# 3_Sensor.net
KiCad netlist of a schematic drawn in Altium Designer
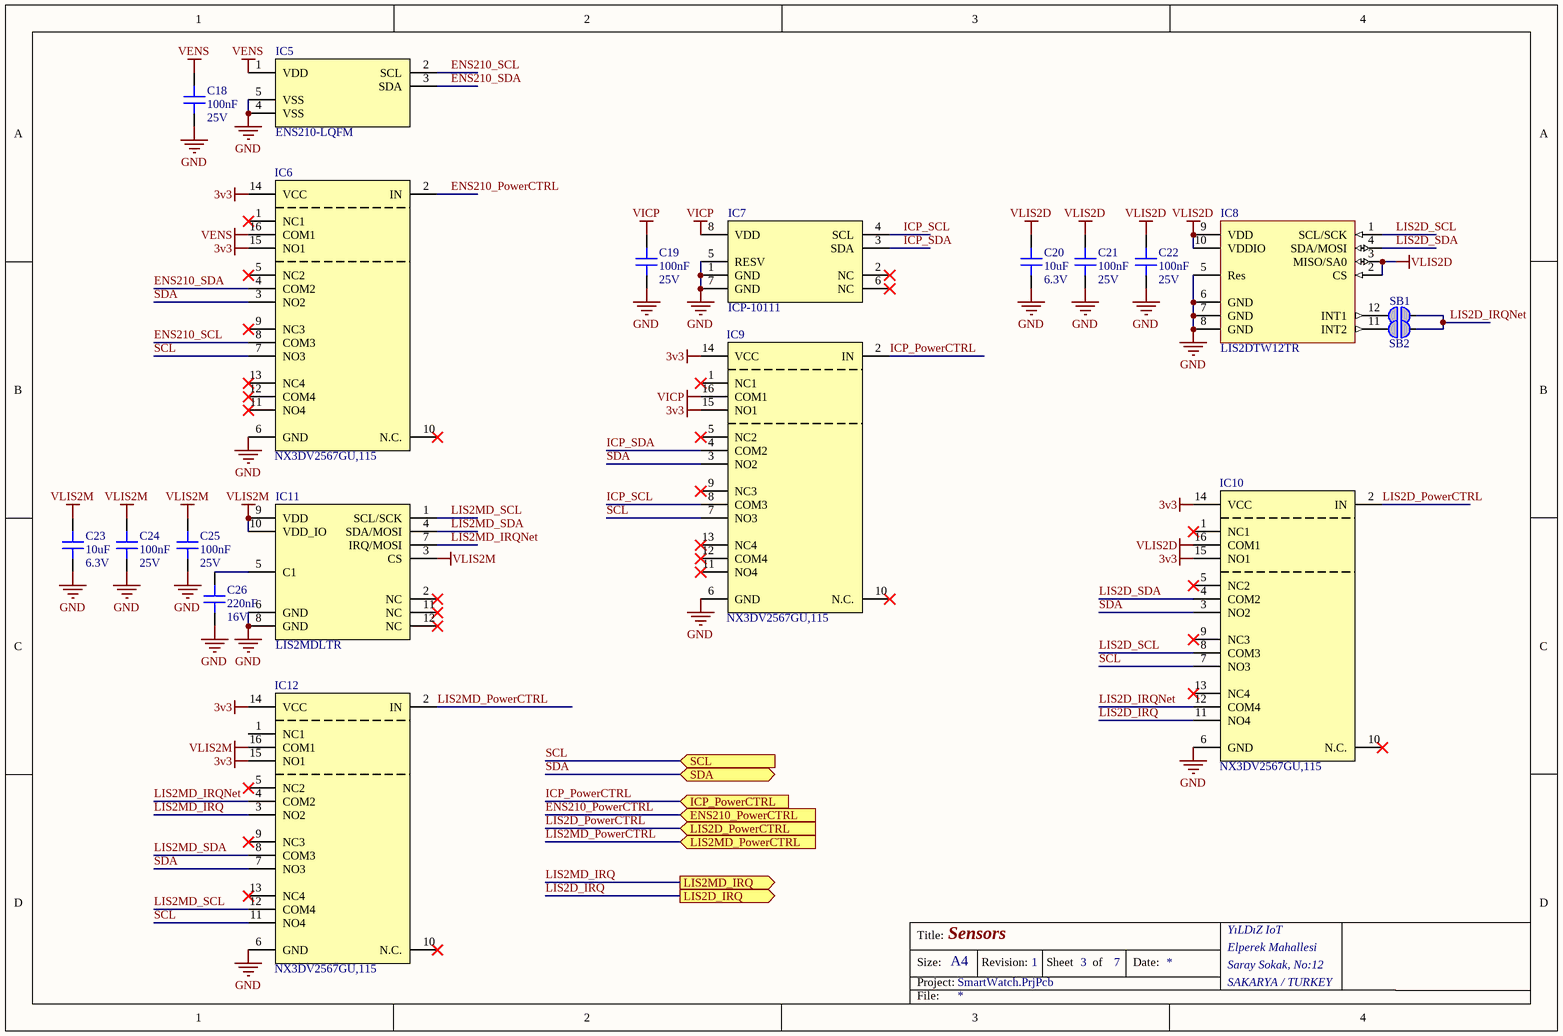
[diagram p0: [3] Sensor.SchDoc]

(export (version "E")
  (design (tool "Eeschema 10.0.6"))
  (components
    (comp (ref "C18")
      (value "100nF")
      (footprint "CAP 0402/1005")
      (description "Cap Ceramic 0.1uF 25V X5R 10% Pad SMD 0402 85°C T/R / Multi Layer Ceramic Capacitor (MLCC)")
      (fields
        (field (name "MANUFACTURER") "Samsung")
        (field (name "MANUFACTURER PART NUMBER") "CL05A104KA5NNNC")
        (field (name "VOLTAGE RATING (DC)") "25V")
      )
      (libsource (lib "yildizIoT Library") (part "Capacitor - Ceramic"))
    )
    (comp (ref "C19")
      (value "100nF")
      (footprint "CAP 0402/1005")
      (description "Cap Ceramic 0.1uF 25V X5R 10% Pad SMD 0402 85°C T/R / Multi Layer Ceramic Capacitor (MLCC)")
      (fields
        (field (name "MANUFACTURER") "Samsung")
        (field (name "MANUFACTURER PART NUMBER") "CL05A104KA5NNNC")
        (field (name "VOLTAGE RATING (DC)") "25V")
      )
      (libsource (lib "yildizIoT Library") (part "Capacitor - Ceramic"))
    )
    (comp (ref "C20")
      (value "10uF")
      (footprint "CAP 0402/1005")
      (description "0402 10 uF 6.3 V ±20 % Tolerance X5R Surface Mount Multilayer Ceramic Capacitor")
      (fields
        (field (name "MANUFACTURER") "Murata")
        (field (name "MANUFACTURER PART NUMBER") "GRM155R60J106ME15D")
        (field (name "VOLTAGE RATING") "6.3V")
      )
      (libsource (lib "yildizIoT Library") (part "Capacitor - Ceramic"))
    )
    (comp (ref "C21")
      (value "100nF")
      (footprint "CAP 0402/1005")
      (description "Cap Ceramic 0.1uF 25V X5R 10% Pad SMD 0402 85°C T/R / Multi Layer Ceramic Capacitor (MLCC)")
      (fields
        (field (name "MANUFACTURER") "Samsung")
        (field (name "MANUFACTURER PART NUMBER") "CL05A104KA5NNNC")
        (field (name "VOLTAGE RATING (DC)") "25V")
      )
      (libsource (lib "yildizIoT Library") (part "Capacitor - Ceramic"))
    )
    (comp (ref "C22")
      (value "100nF")
      (footprint "CAP 0402/1005")
      (description "Cap Ceramic 0.1uF 25V X5R 10% Pad SMD 0402 85°C T/R / Multi Layer Ceramic Capacitor (MLCC)")
      (fields
        (field (name "MANUFACTURER") "Samsung")
        (field (name "MANUFACTURER PART NUMBER") "CL05A104KA5NNNC")
        (field (name "VOLTAGE RATING (DC)") "25V")
      )
      (libsource (lib "yildizIoT Library") (part "Capacitor - Ceramic"))
    )
    (comp (ref "C23")
      (value "10uF")
      (footprint "CAP 0402/1005")
      (description "0402 10 uF 6.3 V ±20 % Tolerance X5R Surface Mount Multilayer Ceramic Capacitor")
      (fields
        (field (name "MANUFACTURER") "Murata")
        (field (name "MANUFACTURER PART NUMBER") "GRM155R60J106ME15D")
        (field (name "VOLTAGE RATING") "6.3V")
      )
      (libsource (lib "yildizIoT Library") (part "Capacitor - Ceramic"))
    )
    (comp (ref "C24")
      (value "100nF")
      (footprint "CAP 0402/1005")
      (description "Cap Ceramic 0.1uF 25V X5R 10% Pad SMD 0402 85°C T/R / Multi Layer Ceramic Capacitor (MLCC)")
      (fields
        (field (name "MANUFACTURER") "Samsung")
        (field (name "MANUFACTURER PART NUMBER") "CL05A104KA5NNNC")
        (field (name "VOLTAGE RATING (DC)") "25V")
      )
      (libsource (lib "yildizIoT Library") (part "Capacitor - Ceramic"))
    )
    (comp (ref "C25")
      (value "100nF")
      (footprint "CAP 0402/1005")
      (description "Cap Ceramic 0.1uF 25V X5R 10% Pad SMD 0402 85°C T/R / Multi Layer Ceramic Capacitor (MLCC)")
      (fields
        (field (name "MANUFACTURER") "Samsung")
        (field (name "MANUFACTURER PART NUMBER") "CL05A104KA5NNNC")
        (field (name "VOLTAGE RATING (DC)") "25V")
      )
      (libsource (lib "yildizIoT Library") (part "Capacitor - Ceramic"))
    )
    (comp (ref "C26")
      (value "220nF")
      (footprint "CAP 0402/1005")
      (description "Ceramic capacitor SMD-0402 220nF /16V X7R# K +-10%, Samsung, RoHS")
      (fields
        (field (name "MANUFACTURER") "Samsung")
        (field (name "MANUFACTURER PART NUMBER") "CL05B224KO5NNNC")
        (field (name "VOLTAGE RATING") "16V")
      )
      (libsource (lib "yildizIoT Library") (part "Capacitor - Ceramic"))
    )
    (comp (ref "IC5")
      (value "ENS210-LQFM")
      (footprint "SCIONSENSE ENS210LQFM")
      (description "ENS210 Series 3.6V 100%RH Relative Humidity & Temperature Sensor w/I²C Interface")
      (fields (field (name "MANUFACTURER") "ScioSense"))
      (libsource (lib "yildizIoT Library") (part "SCIOSENSE ENS210-LQFM"))
    )
    (comp (ref "IC6")
      (value "NX3DV2567GU,115")
      (footprint "NXP XQFN16")
      (description "NX3DV2567 Series 4.3 V 10.5 Ohm 4PDT Low-Ohmic Analog Switch - XQFN-16")
      (fields (field (name "MANUFACTURER") "NXP Semiconductors"))
      (libsource (lib "yildizIoT Library") (part "NXP NX3DV2567GU,115"))
    )
    (comp (ref "IC7")
      (value "ICP-10111")
      (footprint "TDK ICP10111")
      (description "Barometric Pressure/Temperature Sensor Digital 30kPa to 110kPa/-20 to 65°C 8-Pin LGA T/R")
      (fields (field (name "MANUFACTURER") "TDK InvenSense"))
      (libsource (lib "yildizIoT Library") (part "TDK ICP-10111"))
    )
    (comp (ref "IC8")
      (value "LIS2DTW12TR")
      (footprint "ST LGA-12 2x2x0.7")
      (description "3-axis MEMS Accelerometer and Temperature Sensor Digital Output 1.8V 12-Pin LGA T/R")
      (fields (field (name "MANUFACTURER") "STMicroelectronics"))
      (libsource (lib "yildizIoT Library") (part "ST LIS2DE12TR"))
    )
    (comp (ref "IC9")
      (value "NX3DV2567GU,115")
      (footprint "NXP XQFN16")
      (description "NX3DV2567 Series 4.3 V 10.5 Ohm 4PDT Low-Ohmic Analog Switch - XQFN-16")
      (fields (field (name "MANUFACTURER") "NXP Semiconductors"))
      (libsource (lib "yildizIoT Library") (part "NXP NX3DV2567GU,115"))
    )
    (comp (ref "IC10")
      (value "NX3DV2567GU,115")
      (footprint "NXP XQFN16")
      (description "NX3DV2567 Series 4.3 V 10.5 Ohm 4PDT Low-Ohmic Analog Switch - XQFN-16")
      (fields (field (name "MANUFACTURER") "NXP Semiconductors"))
      (libsource (lib "yildizIoT Library") (part "NXP NX3DV2567GU,115"))
    )
    (comp (ref "IC11")
      (value "LIS2MDLTR")
      (footprint "ST LGA-12 2x2x0.7")
      (description "LIS2MDL Series 3.6V 50 Hz High Performance 3-Axis Digital Magnetic Sensor-LGA-12")
      (fields (field (name "MANUFACTURER") "STMicroelectronics"))
      (libsource (lib "yildizIoT Library") (part "ST LIS2MDLTR"))
    )
    (comp (ref "IC12")
      (value "NX3DV2567GU,115")
      (footprint "NXP XQFN16")
      (description "NX3DV2567 Series 4.3 V 10.5 Ohm 4PDT Low-Ohmic Analog Switch - XQFN-16")
      (fields (field (name "MANUFACTURER") "NXP Semiconductors"))
      (libsource (lib "yildizIoT Library") (part "NXP NX3DV2567GU,115"))
    )
    (comp (ref "SB1")
      (value "~")
      (footprint "Solderbridge-Circular")
      (description "Solderbridge")
      (libsource (lib "yildizIoT Library") (part "SOLDERBRIDGE"))
    )
    (comp (ref "SB2")
      (value "~")
      (footprint "Solderbridge-Circular")
      (description "Solderbridge")
      (libsource (lib "yildizIoT Library") (part "SOLDERBRIDGE"))
    )
  )
  (nets
    (net (code "1") (name "/ENS210_PowerCTRL") (class "Default")
      (node (ref "IC6") (pin "2") (pinfunction "IN_2") (pintype "passive"))
    )
    (net (code "2") (name "/ENS210_SCL") (class "Default")
      (node (ref "IC5") (pin "2") (pinfunction "SCL_2") (pintype "passive"))
      (node (ref "IC6") (pin "8") (pinfunction "COM3_8") (pintype "passive"))
    )
    (net (code "3") (name "/ENS210_SDA") (class "Default")
      (node (ref "IC5") (pin "3") (pinfunction "SDA_3") (pintype "passive"))
      (node (ref "IC6") (pin "4") (pinfunction "COM2_4") (pintype "passive"))
    )
    (net (code "4") (name "/ICP_PowerCTRL") (class "Default")
      (node (ref "IC9") (pin "2") (pinfunction "IN_2") (pintype "passive"))
    )
    (net (code "5") (name "/ICP_SCL") (class "Default")
      (node (ref "IC7") (pin "4") (pinfunction "SCL_4") (pintype "passive"))
      (node (ref "IC9") (pin "8") (pinfunction "COM3_8") (pintype "passive"))
    )
    (net (code "6") (name "/ICP_SDA") (class "Default")
      (node (ref "IC7") (pin "3") (pinfunction "SDA_3") (pintype "passive"))
      (node (ref "IC9") (pin "4") (pinfunction "COM2_4") (pintype "passive"))
    )
    (net (code "7") (name "/LIS2D_IRQ") (class "Default")
      (node (ref "IC10") (pin "11") (pinfunction "NO4_11") (pintype "passive"))
    )
    (net (code "8") (name "/LIS2D_IRQNet") (class "Default")
      (node (ref "IC10") (pin "12") (pinfunction "COM4_12") (pintype "passive"))
      (node (ref "SB1") (pin "2") (pinfunction "2_2") (pintype "passive"))
      (node (ref "SB2") (pin "2") (pinfunction "2_2") (pintype "passive"))
    )
    (net (code "9") (name "/LIS2D_PowerCTRL") (class "Default")
      (node (ref "IC10") (pin "2") (pinfunction "IN_2") (pintype "passive"))
    )
    (net (code "10") (name "/LIS2D_SCL") (class "Default")
      (node (ref "IC10") (pin "8") (pinfunction "COM3_8") (pintype "passive"))
      (node (ref "IC8") (pin "1") (pinfunction "SCL/SCK_1") (pintype "input"))
    )
    (net (code "11") (name "/LIS2D_SDA") (class "Default")
      (node (ref "IC10") (pin "4") (pinfunction "COM2_4") (pintype "passive"))
      (node (ref "IC8") (pin "4") (pinfunction "SDA/MOSI_4") (pintype "bidirectional"))
    )
    (net (code "12") (name "/LIS2MD_IRQ") (class "Default")
      (node (ref "IC12") (pin "3") (pinfunction "NO2_3") (pintype "passive"))
    )
    (net (code "13") (name "/LIS2MD_IRQNet") (class "Default")
      (node (ref "IC11") (pin "7") (pinfunction "IRQ/MOSI_7") (pintype "passive"))
      (node (ref "IC12") (pin "4") (pinfunction "COM2_4") (pintype "passive"))
    )
    (net (code "14") (name "/LIS2MD_PowerCTRL") (class "Default")
      (node (ref "IC12") (pin "2") (pinfunction "IN_2") (pintype "passive"))
    )
    (net (code "15") (name "/LIS2MD_SCL") (class "Default")
      (node (ref "IC11") (pin "1") (pinfunction "SCL/SCK_1") (pintype "passive"))
      (node (ref "IC12") (pin "12") (pinfunction "COM4_12") (pintype "passive"))
    )
    (net (code "16") (name "/LIS2MD_SDA") (class "Default")
      (node (ref "IC11") (pin "4") (pinfunction "SDA/MOSI_4") (pintype "passive"))
      (node (ref "IC12") (pin "8") (pinfunction "COM3_8") (pintype "passive"))
    )
    (net (code "17") (name "/SCL") (class "Default")
      (node (ref "IC10") (pin "7") (pinfunction "NO3_7") (pintype "passive"))
      (node (ref "IC12") (pin "11") (pinfunction "NO4_11") (pintype "passive"))
      (node (ref "IC6") (pin "7") (pinfunction "NO3_7") (pintype "passive"))
      (node (ref "IC9") (pin "7") (pinfunction "NO3_7") (pintype "passive"))
    )
    (net (code "18") (name "/SDA") (class "Default")
      (node (ref "IC10") (pin "3") (pinfunction "NO2_3") (pintype "passive"))
      (node (ref "IC12") (pin "7") (pinfunction "NO3_7") (pintype "passive"))
      (node (ref "IC6") (pin "3") (pinfunction "NO2_3") (pintype "passive"))
      (node (ref "IC9") (pin "3") (pinfunction "NO2_3") (pintype "passive"))
    )
    (net (code "19") (name "3v3") (class "Default")
      (node (ref "IC10") (pin "14") (pinfunction "VCC_14") (pintype "passive"))
      (node (ref "IC10") (pin "15") (pinfunction "NO1_15") (pintype "passive"))
      (node (ref "IC12") (pin "14") (pinfunction "VCC_14") (pintype "passive"))
      (node (ref "IC12") (pin "15") (pinfunction "NO1_15") (pintype "passive"))
      (node (ref "IC6") (pin "14") (pinfunction "VCC_14") (pintype "passive"))
      (node (ref "IC6") (pin "15") (pinfunction "NO1_15") (pintype "passive"))
      (node (ref "IC9") (pin "14") (pinfunction "VCC_14") (pintype "passive"))
      (node (ref "IC9") (pin "15") (pinfunction "NO1_15") (pintype "passive"))
    )
    (net (code "20") (name "GND") (class "Default")
      (node (ref "C18") (pin "1") (pinfunction "1_1") (pintype "passive"))
      (node (ref "C19") (pin "1") (pinfunction "1_1") (pintype "passive"))
      (node (ref "C20") (pin "1") (pinfunction "1_1") (pintype "passive"))
      (node (ref "C21") (pin "1") (pinfunction "1_1") (pintype "passive"))
      (node (ref "C22") (pin "1") (pinfunction "1_1") (pintype "passive"))
      (node (ref "C23") (pin "1") (pinfunction "1_1") (pintype "passive"))
      (node (ref "C24") (pin "1") (pinfunction "1_1") (pintype "passive"))
      (node (ref "C25") (pin "1") (pinfunction "1_1") (pintype "passive"))
      (node (ref "C26") (pin "1") (pinfunction "1_1") (pintype "passive"))
      (node (ref "IC10") (pin "6") (pinfunction "GND_6") (pintype "passive"))
      (node (ref "IC11") (pin "6") (pinfunction "GND_6") (pintype "passive"))
      (node (ref "IC11") (pin "8") (pinfunction "GND_8") (pintype "passive"))
      (node (ref "IC12") (pin "6") (pinfunction "GND_6") (pintype "passive"))
      (node (ref "IC5") (pin "4") (pinfunction "VSS_4") (pintype "passive"))
      (node (ref "IC5") (pin "5") (pinfunction "VSS_5") (pintype "passive"))
      (node (ref "IC6") (pin "6") (pinfunction "GND_6") (pintype "passive"))
      (node (ref "IC7") (pin "1") (pinfunction "GND_1") (pintype "passive"))
      (node (ref "IC7") (pin "5") (pinfunction "RESV_5") (pintype "passive"))
      (node (ref "IC7") (pin "7") (pinfunction "GND_7") (pintype "passive"))
      (node (ref "IC8") (pin "5") (pinfunction "Res_5") (pintype "passive"))
      (node (ref "IC8") (pin "6") (pinfunction "GND_6") (pintype "power_in"))
      (node (ref "IC8") (pin "7") (pinfunction "GND_7") (pintype "power_in"))
      (node (ref "IC8") (pin "8") (pinfunction "GND_8") (pintype "power_in"))
      (node (ref "IC9") (pin "6") (pinfunction "GND_6") (pintype "passive"))
    )
    (net (code "21") (name "Net-(IC8-INT1)") (class "Default")
      (node (ref "IC8") (pin "12") (pinfunction "INT1_12") (pintype "output"))
      (node (ref "SB1") (pin "1") (pinfunction "1_1") (pintype "passive"))
    )
    (net (code "22") (name "Net-(IC8-INT2)") (class "Default")
      (node (ref "IC8") (pin "11") (pinfunction "INT2_11") (pintype "output"))
      (node (ref "SB2") (pin "1") (pinfunction "1_1") (pintype "passive"))
    )
    (net (code "23") (name "Net-(IC11-C1)") (class "Default")
      (node (ref "C26") (pin "2") (pinfunction "2_2") (pintype "passive"))
      (node (ref "IC11") (pin "5") (pinfunction "C1_5") (pintype "passive"))
    )
    (net (code "24") (name "VENS") (class "Default")
      (node (ref "C18") (pin "2") (pinfunction "2_2") (pintype "passive"))
      (node (ref "IC5") (pin "1") (pinfunction "VDD_1") (pintype "passive"))
      (node (ref "IC6") (pin "16") (pinfunction "COM1_16") (pintype "passive"))
    )
    (net (code "25") (name "VICP") (class "Default")
      (node (ref "C19") (pin "2") (pinfunction "2_2") (pintype "passive"))
      (node (ref "IC7") (pin "8") (pinfunction "VDD_8") (pintype "passive"))
      (node (ref "IC9") (pin "16") (pinfunction "COM1_16") (pintype "passive"))
    )
    (net (code "26") (name "VLIS2D") (class "Default")
      (node (ref "C20") (pin "2") (pinfunction "2_2") (pintype "passive"))
      (node (ref "C21") (pin "2") (pinfunction "2_2") (pintype "passive"))
      (node (ref "C22") (pin "2") (pinfunction "2_2") (pintype "passive"))
      (node (ref "IC10") (pin "16") (pinfunction "COM1_16") (pintype "passive"))
      (node (ref "IC8") (pin "10") (pinfunction "VDDIO_10") (pintype "power_in"))
      (node (ref "IC8") (pin "2") (pinfunction "CS_2") (pintype "input"))
      (node (ref "IC8") (pin "3") (pinfunction "MISO/SA0_3") (pintype "bidirectional"))
      (node (ref "IC8") (pin "9") (pinfunction "VDD_9") (pintype "power_in"))
    )
    (net (code "27") (name "VLIS2M") (class "Default")
      (node (ref "C23") (pin "2") (pinfunction "2_2") (pintype "passive"))
      (node (ref "C24") (pin "2") (pinfunction "2_2") (pintype "passive"))
      (node (ref "C25") (pin "2") (pinfunction "2_2") (pintype "passive"))
      (node (ref "IC11") (pin "10") (pinfunction "VDD_IO_10") (pintype "passive"))
      (node (ref "IC11") (pin "3") (pinfunction "CS_3") (pintype "passive"))
      (node (ref "IC11") (pin "9") (pinfunction "VDD_9") (pintype "passive"))
      (node (ref "IC12") (pin "16") (pinfunction "COM1_16") (pintype "passive"))
    )
    (net (code "28") (name "unconnected-(IC6-COM4-Pad12)") (class "Default")
      (node (ref "IC6") (pin "12") (pinfunction "COM4_12") (pintype "passive+no_connect"))
    )
    (net (code "29") (name "unconnected-(IC6-N.C.-Pad10)") (class "Default")
      (node (ref "IC6") (pin "10") (pinfunction "N.C._10") (pintype "passive+no_connect"))
    )
    (net (code "30") (name "unconnected-(IC6-NC1-Pad1)") (class "Default")
      (node (ref "IC6") (pin "1") (pinfunction "NC1_1") (pintype "passive+no_connect"))
    )
    (net (code "31") (name "unconnected-(IC6-NC2-Pad5)") (class "Default")
      (node (ref "IC6") (pin "5") (pinfunction "NC2_5") (pintype "passive+no_connect"))
    )
    (net (code "32") (name "unconnected-(IC6-NC3-Pad9)") (class "Default")
      (node (ref "IC6") (pin "9") (pinfunction "NC3_9") (pintype "passive+no_connect"))
    )
    (net (code "33") (name "unconnected-(IC6-NC4-Pad13)") (class "Default")
      (node (ref "IC6") (pin "13") (pinfunction "NC4_13") (pintype "passive+no_connect"))
    )
    (net (code "34") (name "unconnected-(IC6-NO4-Pad11)") (class "Default")
      (node (ref "IC6") (pin "11") (pinfunction "NO4_11") (pintype "passive+no_connect"))
    )
    (net (code "35") (name "unconnected-(IC7-NC-Pad2)") (class "Default")
      (node (ref "IC7") (pin "2") (pinfunction "NC_2") (pintype "passive+no_connect"))
    )
    (net (code "36") (name "unconnected-(IC7-NC-Pad6)") (class "Default")
      (node (ref "IC7") (pin "6") (pinfunction "NC_6") (pintype "passive+no_connect"))
    )
    (net (code "37") (name "unconnected-(IC9-COM4-Pad12)") (class "Default")
      (node (ref "IC9") (pin "12") (pinfunction "COM4_12") (pintype "passive+no_connect"))
    )
    (net (code "38") (name "unconnected-(IC9-N.C.-Pad10)") (class "Default")
      (node (ref "IC9") (pin "10") (pinfunction "N.C._10") (pintype "passive+no_connect"))
    )
    (net (code "39") (name "unconnected-(IC9-NC1-Pad1)") (class "Default")
      (node (ref "IC9") (pin "1") (pinfunction "NC1_1") (pintype "passive+no_connect"))
    )
    (net (code "40") (name "unconnected-(IC9-NC2-Pad5)") (class "Default")
      (node (ref "IC9") (pin "5") (pinfunction "NC2_5") (pintype "passive+no_connect"))
    )
    (net (code "41") (name "unconnected-(IC9-NC3-Pad9)") (class "Default")
      (node (ref "IC9") (pin "9") (pinfunction "NC3_9") (pintype "passive+no_connect"))
    )
    (net (code "42") (name "unconnected-(IC9-NC4-Pad13)") (class "Default")
      (node (ref "IC9") (pin "13") (pinfunction "NC4_13") (pintype "passive+no_connect"))
    )
    (net (code "43") (name "unconnected-(IC9-NO4-Pad11)") (class "Default")
      (node (ref "IC9") (pin "11") (pinfunction "NO4_11") (pintype "passive+no_connect"))
    )
    (net (code "44") (name "unconnected-(IC10-N.C.-Pad10)") (class "Default")
      (node (ref "IC10") (pin "10") (pinfunction "N.C._10") (pintype "passive+no_connect"))
    )
    (net (code "45") (name "unconnected-(IC10-NC1-Pad1)") (class "Default")
      (node (ref "IC10") (pin "1") (pinfunction "NC1_1") (pintype "passive+no_connect"))
    )
    (net (code "46") (name "unconnected-(IC10-NC2-Pad5)") (class "Default")
      (node (ref "IC10") (pin "5") (pinfunction "NC2_5") (pintype "passive+no_connect"))
    )
    (net (code "47") (name "unconnected-(IC10-NC3-Pad9)") (class "Default")
      (node (ref "IC10") (pin "9") (pinfunction "NC3_9") (pintype "passive+no_connect"))
    )
    (net (code "48") (name "unconnected-(IC10-NC4-Pad13)") (class "Default")
      (node (ref "IC10") (pin "13") (pinfunction "NC4_13") (pintype "passive+no_connect"))
    )
    (net (code "49") (name "unconnected-(IC11-NC-Pad2)") (class "Default")
      (node (ref "IC11") (pin "2") (pinfunction "NC_2") (pintype "passive+no_connect"))
    )
    (net (code "50") (name "unconnected-(IC11-NC-Pad11)") (class "Default")
      (node (ref "IC11") (pin "11") (pinfunction "NC_11") (pintype "passive+no_connect"))
    )
    (net (code "51") (name "unconnected-(IC11-NC-Pad12)") (class "Default")
      (node (ref "IC11") (pin "12") (pinfunction "NC_12") (pintype "passive+no_connect"))
    )
    (net (code "52") (name "unconnected-(IC12-N.C.-Pad10)") (class "Default")
      (node (ref "IC12") (pin "10") (pinfunction "N.C._10") (pintype "passive+no_connect"))
    )
    (net (code "53") (name "unconnected-(IC12-NC1-Pad1)") (class "Default")
      (node (ref "IC12") (pin "1") (pinfunction "NC1_1") (pintype "passive"))
    )
    (net (code "54") (name "unconnected-(IC12-NC2-Pad5)") (class "Default")
      (node (ref "IC12") (pin "5") (pinfunction "NC2_5") (pintype "passive+no_connect"))
    )
    (net (code "55") (name "unconnected-(IC12-NC3-Pad9)") (class "Default")
      (node (ref "IC12") (pin "9") (pinfunction "NC3_9") (pintype "passive+no_connect"))
    )
    (net (code "56") (name "unconnected-(IC12-NC4-Pad13)") (class "Default")
      (node (ref "IC12") (pin "13") (pinfunction "NC4_13") (pintype "passive+no_connect"))
    )
  )
)
